# Low_jitter_CLK_bypass.net
KiCad netlist of a schematic drawn in Altium Designer
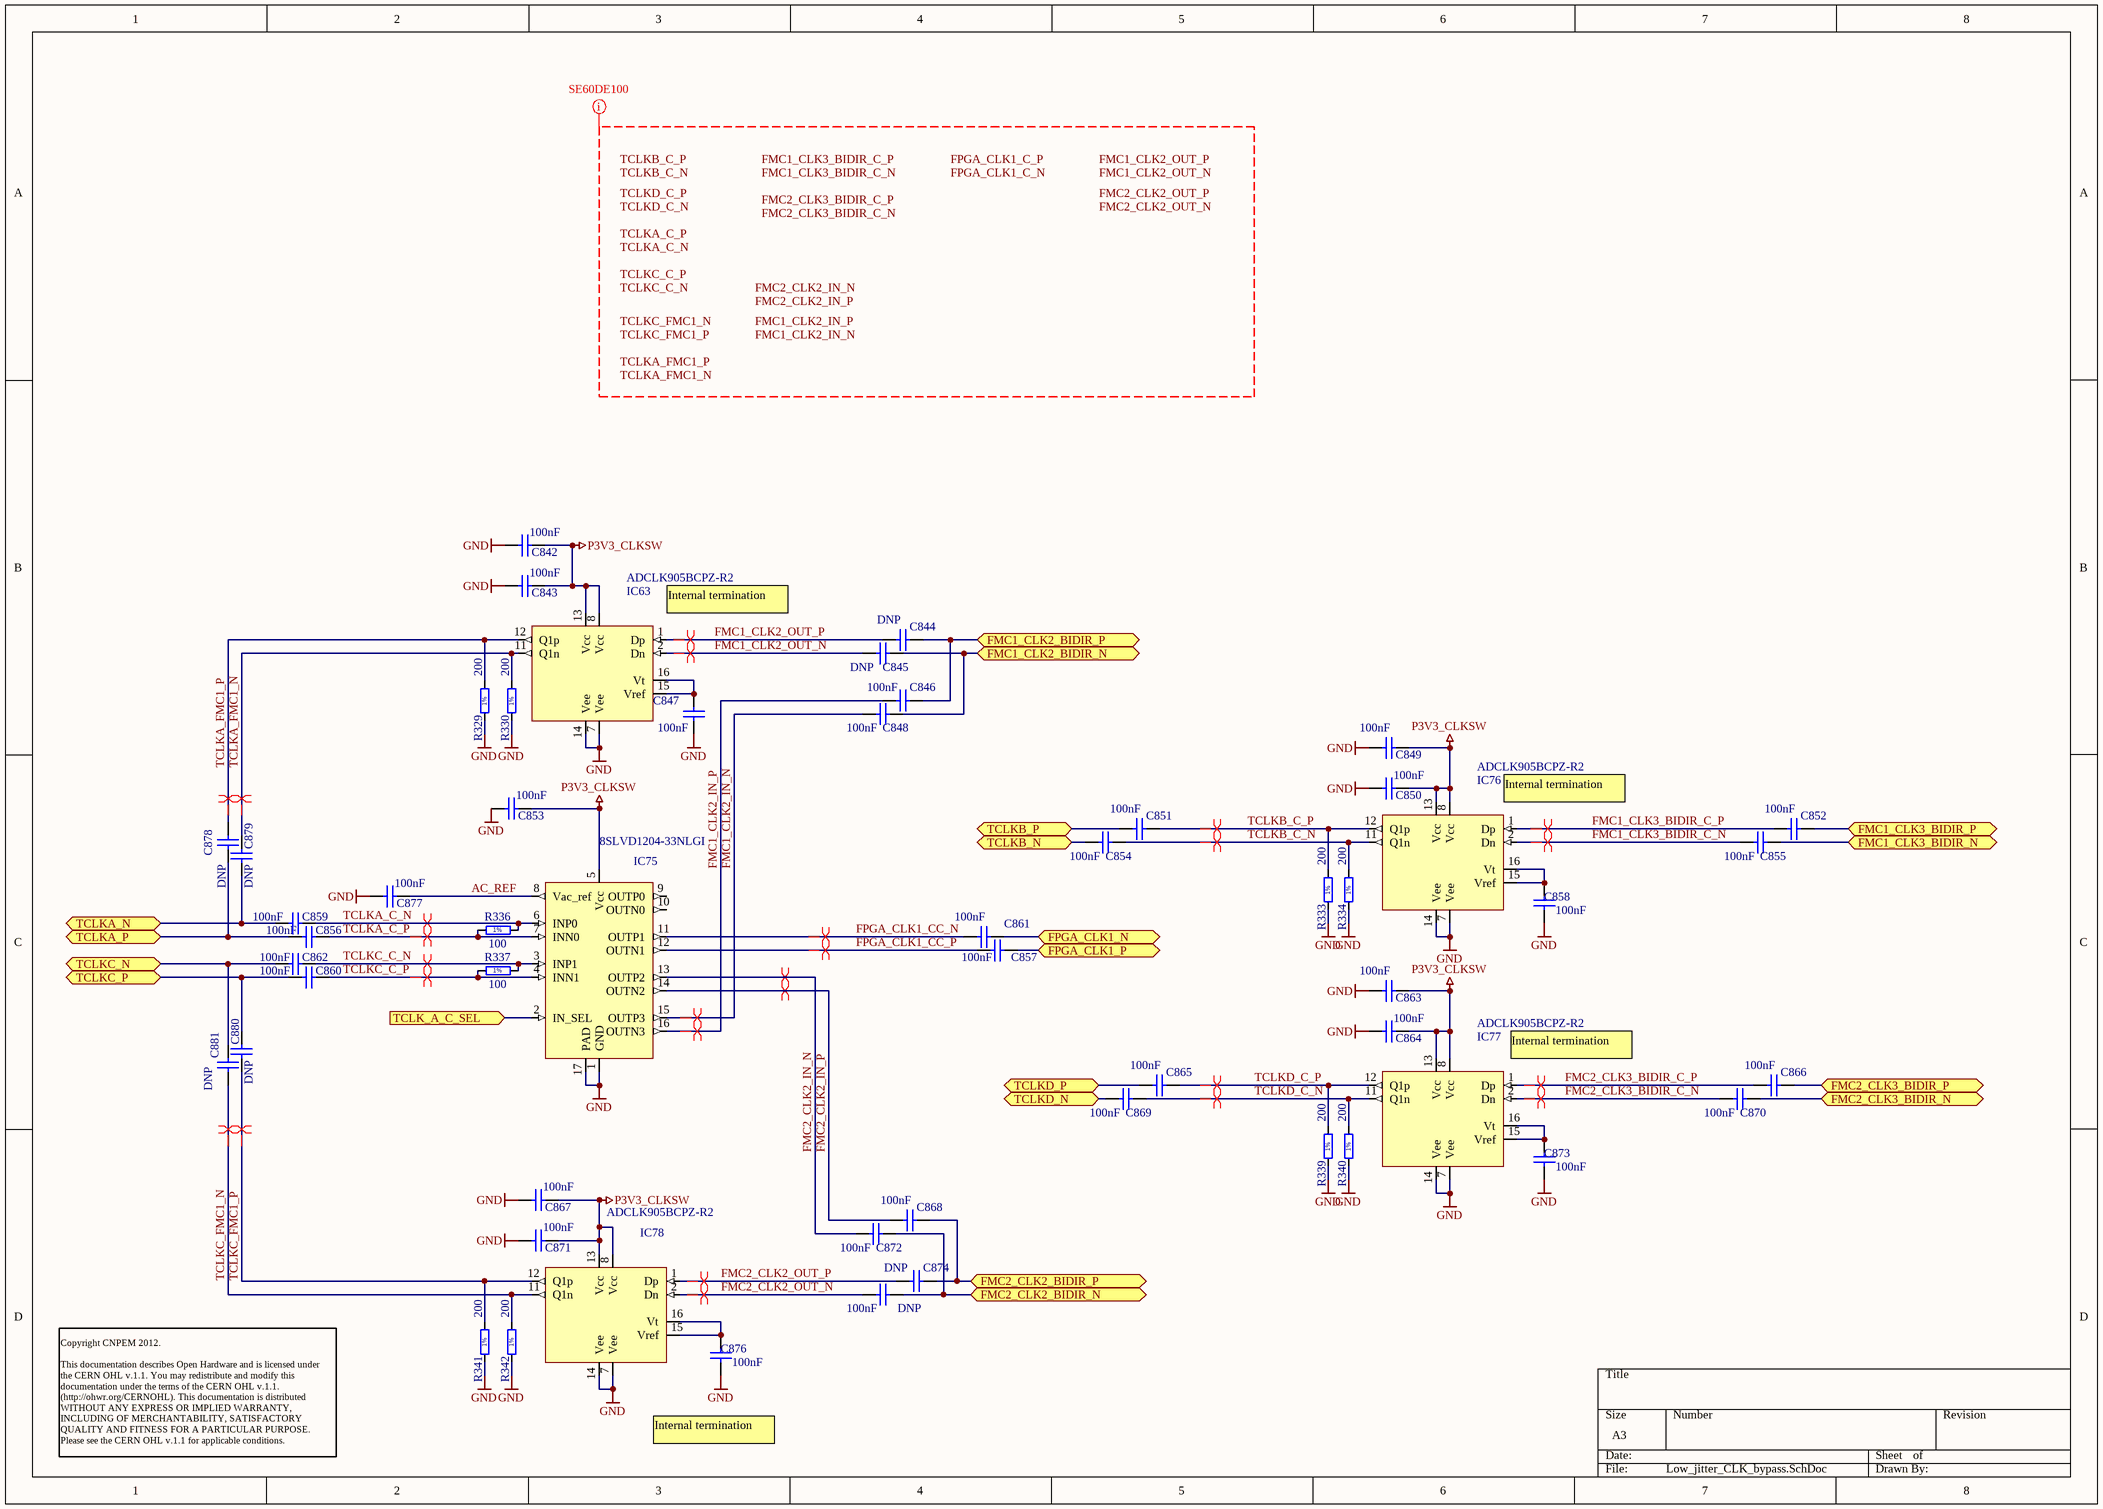
[diagram p0: Low_jitter_CLK_bypass.SchDoc]

(export (version "E")
  (design (tool "Eeschema 10.0.6"))
  (components
    (comp (ref "C842")
      (value "100nF")
      (footprint "CAPC0603X33N")
      (description "Non-polarised capacitor")
      (fields
        (field (name "PART NUMBER") "CC0201_100NF_6.3V_10%_X5R")
        (field (name "VOLTAGE") "6.3V")
        (field (name "AUTHOR") "CERN DEM JLC")
      )
      (libsource (lib "Capacitors") (part "Capacitor - non polarized"))
    )
    (comp (ref "C843")
      (value "100nF")
      (footprint "CAPC0603X33N")
      (description "Non-polarised capacitor")
      (fields
        (field (name "PART NUMBER") "CC0201_100NF_6.3V_10%_X5R")
        (field (name "VOLTAGE") "6.3V")
        (field (name "AUTHOR") "CERN DEM JLC")
      )
      (libsource (lib "Capacitors") (part "Capacitor - non polarized"))
    )
    (comp (ref "C844")
      (value "DNP")
      (footprint "CAPC0603X33N")
      (description "Non-polarised capacitor")
      (fields
        (field (name "PART NUMBER") "CC0201_100NF_6.3V_10%_X5R")
        (field (name "VOLTAGE") "6.3V")
        (field (name "AUTHOR") "CERN DEM JLC")
      )
      (libsource (lib "Capacitors") (part "Capacitor - non polarized"))
    )
    (comp (ref "C845")
      (value "DNP")
      (footprint "CAPC0603X33N")
      (description "Non-polarised capacitor")
      (fields
        (field (name "PART NUMBER") "CC0201_100NF_6.3V_10%_X5R")
        (field (name "VOLTAGE") "6.3V")
        (field (name "AUTHOR") "CERN DEM JLC")
      )
      (libsource (lib "Capacitors") (part "Capacitor - non polarized"))
    )
    (comp (ref "C846")
      (value "100nF")
      (footprint "CAPC0603X33N")
      (description "Non-polarised capacitor")
      (fields
        (field (name "PART NUMBER") "CC0201_100NF_6.3V_10%_X5R")
        (field (name "VOLTAGE") "6.3V")
        (field (name "AUTHOR") "CERN DEM JLC")
      )
      (libsource (lib "Capacitors") (part "Capacitor - non polarized"))
    )
    (comp (ref "C847")
      (value "100nF")
      (footprint "CAPC0603X33N")
      (description "Non-polarised capacitor")
      (fields
        (field (name "PART NUMBER") "CC0201_100NF_6.3V_10%_X5R")
        (field (name "VOLTAGE") "6.3V")
        (field (name "AUTHOR") "CERN DEM JLC")
      )
      (libsource (lib "Capacitors") (part "Capacitor - non polarized"))
    )
    (comp (ref "C848")
      (value "100nF")
      (footprint "CAPC0603X33N")
      (description "Non-polarised capacitor")
      (fields
        (field (name "PART NUMBER") "CC0201_100NF_6.3V_10%_X5R")
        (field (name "VOLTAGE") "6.3V")
        (field (name "AUTHOR") "CERN DEM JLC")
      )
      (libsource (lib "Capacitors") (part "Capacitor - non polarized"))
    )
    (comp (ref "C849")
      (value "100nF")
      (footprint "CAPC0603X33N")
      (description "Non-polarised capacitor")
      (fields
        (field (name "PART NUMBER") "CC0201_100NF_6.3V_10%_X5R")
        (field (name "VOLTAGE") "6.3V")
        (field (name "AUTHOR") "CERN DEM JLC")
      )
      (libsource (lib "Capacitors") (part "Capacitor - non polarized"))
    )
    (comp (ref "C850")
      (value "100nF")
      (footprint "CAPC0603X33N")
      (description "Non-polarised capacitor")
      (fields
        (field (name "PART NUMBER") "CC0201_100NF_6.3V_10%_X5R")
        (field (name "VOLTAGE") "6.3V")
        (field (name "AUTHOR") "CERN DEM JLC")
      )
      (libsource (lib "Capacitors") (part "Capacitor - non polarized"))
    )
    (comp (ref "C851")
      (value "100nF")
      (footprint "CAPC0603X33N")
      (description "Non-polarised capacitor")
      (fields
        (field (name "PART NUMBER") "CC0201_100NF_6.3V_10%_X5R")
        (field (name "VOLTAGE") "6.3V")
        (field (name "AUTHOR") "CERN DEM JLC")
      )
      (libsource (lib "Capacitors") (part "Capacitor - non polarized"))
    )
    (comp (ref "C852")
      (value "100nF")
      (footprint "CAPC0603X33N")
      (description "Non-polarised capacitor")
      (fields
        (field (name "PART NUMBER") "CC0201_100NF_6.3V_10%_X5R")
        (field (name "VOLTAGE") "6.3V")
        (field (name "AUTHOR") "CERN DEM JLC")
      )
      (libsource (lib "Capacitors") (part "Capacitor - non polarized"))
    )
    (comp (ref "C853")
      (value "100nF")
      (footprint "CAPC0603X33N")
      (description "Non-polarised capacitor")
      (fields
        (field (name "PART NUMBER") "CC0201_100NF_6.3V_10%_X5R")
        (field (name "VOLTAGE") "6.3V")
        (field (name "AUTHOR") "CERN DEM JLC")
      )
      (libsource (lib "Capacitors") (part "Capacitor - non polarized"))
    )
    (comp (ref "C854")
      (value "100nF")
      (footprint "CAPC0603X33N")
      (description "Non-polarised capacitor")
      (fields
        (field (name "PART NUMBER") "CC0201_100NF_6.3V_10%_X5R")
        (field (name "VOLTAGE") "6.3V")
        (field (name "AUTHOR") "CERN DEM JLC")
      )
      (libsource (lib "Capacitors") (part "Capacitor - non polarized"))
    )
    (comp (ref "C855")
      (value "100nF")
      (footprint "CAPC0603X33N")
      (description "Non-polarised capacitor")
      (fields
        (field (name "PART NUMBER") "CC0201_100NF_6.3V_10%_X5R")
        (field (name "VOLTAGE") "6.3V")
        (field (name "AUTHOR") "CERN DEM JLC")
      )
      (libsource (lib "Capacitors") (part "Capacitor - non polarized"))
    )
    (comp (ref "C856")
      (value "100nF")
      (footprint "CAPC0603X33N")
      (description "Non-polarised capacitor")
      (fields
        (field (name "PART NUMBER") "CC0201_100NF_6.3V_10%_X5R")
        (field (name "VOLTAGE") "6.3V")
        (field (name "AUTHOR") "CERN DEM JLC")
      )
      (libsource (lib "Capacitors") (part "Capacitor - non polarized"))
    )
    (comp (ref "C857")
      (value "100nF")
      (footprint "CAPC0603X33N")
      (description "Non-polarised capacitor")
      (fields
        (field (name "PART NUMBER") "CC0201_100NF_6.3V_10%_X5R")
        (field (name "VOLTAGE") "6.3V")
        (field (name "AUTHOR") "CERN DEM JLC")
      )
      (libsource (lib "Capacitors") (part "Capacitor - non polarized"))
    )
    (comp (ref "C858")
      (value "100nF")
      (footprint "CAPC0603X33N")
      (description "Non-polarised capacitor")
      (fields
        (field (name "PART NUMBER") "CC0201_100NF_6.3V_10%_X5R")
        (field (name "VOLTAGE") "6.3V")
        (field (name "AUTHOR") "CERN DEM JLC")
      )
      (libsource (lib "Capacitors") (part "Capacitor - non polarized"))
    )
    (comp (ref "C859")
      (value "100nF")
      (footprint "CAPC0603X33N")
      (description "Non-polarised capacitor")
      (fields
        (field (name "PART NUMBER") "CC0201_100NF_6.3V_10%_X5R")
        (field (name "VOLTAGE") "6.3V")
        (field (name "AUTHOR") "CERN DEM JLC")
      )
      (libsource (lib "Capacitors") (part "Capacitor - non polarized"))
    )
    (comp (ref "C860")
      (value "100nF")
      (footprint "CAPC0603X33N")
      (description "Non-polarised capacitor")
      (fields
        (field (name "PART NUMBER") "CC0201_100NF_6.3V_10%_X5R")
        (field (name "VOLTAGE") "6.3V")
        (field (name "AUTHOR") "CERN DEM JLC")
      )
      (libsource (lib "Capacitors") (part "Capacitor - non polarized"))
    )
    (comp (ref "C861")
      (value "100nF")
      (footprint "CAPC0603X33N")
      (description "Non-polarised capacitor")
      (fields
        (field (name "PART NUMBER") "CC0201_100NF_6.3V_10%_X5R")
        (field (name "VOLTAGE") "6.3V")
        (field (name "AUTHOR") "CERN DEM JLC")
      )
      (libsource (lib "Capacitors") (part "Capacitor - non polarized"))
    )
    (comp (ref "C862")
      (value "100nF")
      (footprint "CAPC0603X33N")
      (description "Non-polarised capacitor")
      (fields
        (field (name "PART NUMBER") "CC0201_100NF_6.3V_10%_X5R")
        (field (name "VOLTAGE") "6.3V")
        (field (name "AUTHOR") "CERN DEM JLC")
      )
      (libsource (lib "Capacitors") (part "Capacitor - non polarized"))
    )
    (comp (ref "C863")
      (value "100nF")
      (footprint "CAPC0603X33N")
      (description "Non-polarised capacitor")
      (fields
        (field (name "PART NUMBER") "CC0201_100NF_6.3V_10%_X5R")
        (field (name "VOLTAGE") "6.3V")
        (field (name "AUTHOR") "CERN DEM JLC")
      )
      (libsource (lib "Capacitors") (part "Capacitor - non polarized"))
    )
    (comp (ref "C864")
      (value "100nF")
      (footprint "CAPC0603X33N")
      (description "Non-polarised capacitor")
      (fields
        (field (name "PART NUMBER") "CC0201_100NF_6.3V_10%_X5R")
        (field (name "VOLTAGE") "6.3V")
        (field (name "AUTHOR") "CERN DEM JLC")
      )
      (libsource (lib "Capacitors") (part "Capacitor - non polarized"))
    )
    (comp (ref "C865")
      (value "100nF")
      (footprint "CAPC0603X33N")
      (description "Non-polarised capacitor")
      (fields
        (field (name "PART NUMBER") "CC0201_100NF_6.3V_10%_X5R")
        (field (name "VOLTAGE") "6.3V")
        (field (name "AUTHOR") "CERN DEM JLC")
      )
      (libsource (lib "Capacitors") (part "Capacitor - non polarized"))
    )
    (comp (ref "C866")
      (value "100nF")
      (footprint "CAPC0603X33N")
      (description "Non-polarised capacitor")
      (fields
        (field (name "PART NUMBER") "CC0201_100NF_6.3V_10%_X5R")
        (field (name "VOLTAGE") "6.3V")
        (field (name "AUTHOR") "CERN DEM JLC")
      )
      (libsource (lib "Capacitors") (part "Capacitor - non polarized"))
    )
    (comp (ref "C867")
      (value "100nF")
      (footprint "CAPC0603X33N")
      (description "Non-polarised capacitor")
      (fields
        (field (name "PART NUMBER") "CC0201_100NF_6.3V_10%_X5R")
        (field (name "VOLTAGE") "6.3V")
        (field (name "AUTHOR") "CERN DEM JLC")
      )
      (libsource (lib "Capacitors") (part "Capacitor - non polarized"))
    )
    (comp (ref "C868")
      (value "100nF")
      (footprint "CAPC0603X33N")
      (description "Non-polarised capacitor")
      (fields
        (field (name "PART NUMBER") "CC0201_100NF_6.3V_10%_X5R")
        (field (name "VOLTAGE") "6.3V")
        (field (name "AUTHOR") "CERN DEM JLC")
      )
      (libsource (lib "Capacitors") (part "Capacitor - non polarized"))
    )
    (comp (ref "C869")
      (value "100nF")
      (footprint "CAPC0603X33N")
      (description "Non-polarised capacitor")
      (fields
        (field (name "PART NUMBER") "CC0201_100NF_6.3V_10%_X5R")
        (field (name "VOLTAGE") "6.3V")
        (field (name "AUTHOR") "CERN DEM JLC")
      )
      (libsource (lib "Capacitors") (part "Capacitor - non polarized"))
    )
    (comp (ref "C870")
      (value "100nF")
      (footprint "CAPC0603X33N")
      (description "Non-polarised capacitor")
      (fields
        (field (name "PART NUMBER") "CC0201_100NF_6.3V_10%_X5R")
        (field (name "VOLTAGE") "6.3V")
        (field (name "AUTHOR") "CERN DEM JLC")
      )
      (libsource (lib "Capacitors") (part "Capacitor - non polarized"))
    )
    (comp (ref "C871")
      (value "100nF")
      (footprint "CAPC0603X33N")
      (description "Non-polarised capacitor")
      (fields
        (field (name "PART NUMBER") "CC0201_100NF_6.3V_10%_X5R")
        (field (name "VOLTAGE") "6.3V")
        (field (name "AUTHOR") "CERN DEM JLC")
      )
      (libsource (lib "Capacitors") (part "Capacitor - non polarized"))
    )
    (comp (ref "C872")
      (value "100nF")
      (footprint "CAPC0603X33N")
      (description "Non-polarised capacitor")
      (fields
        (field (name "PART NUMBER") "CC0201_100NF_6.3V_10%_X5R")
        (field (name "VOLTAGE") "6.3V")
        (field (name "AUTHOR") "CERN DEM JLC")
      )
      (libsource (lib "Capacitors") (part "Capacitor - non polarized"))
    )
    (comp (ref "C873")
      (value "100nF")
      (footprint "CAPC0603X33N")
      (description "Non-polarised capacitor")
      (fields
        (field (name "PART NUMBER") "CC0201_100NF_6.3V_10%_X5R")
        (field (name "VOLTAGE") "6.3V")
        (field (name "AUTHOR") "CERN DEM JLC")
      )
      (libsource (lib "Capacitors") (part "Capacitor - non polarized"))
    )
    (comp (ref "C874")
      (value "DNP")
      (footprint "CAPC0603X33N")
      (description "Non-polarised capacitor")
      (fields
        (field (name "PART NUMBER") "CC0201_100NF_6.3V_10%_X5R")
        (field (name "VOLTAGE") "6.3V")
        (field (name "AUTHOR") "CERN DEM JLC")
      )
      (libsource (lib "Capacitors") (part "Capacitor - non polarized"))
    )
    (comp (ref "C876")
      (value "100nF")
      (footprint "CAPC0603X33N")
      (description "Non-polarised capacitor")
      (fields
        (field (name "PART NUMBER") "CC0201_100NF_6.3V_10%_X5R")
        (field (name "VOLTAGE") "6.3V")
        (field (name "AUTHOR") "CERN DEM JLC")
      )
      (libsource (lib "Capacitors") (part "Capacitor - non polarized"))
    )
    (comp (ref "C877")
      (value "100nF")
      (footprint "CAPC0603X33N")
      (description "Non-polarised capacitor")
      (fields
        (field (name "PART NUMBER") "CC0201_100NF_6.3V_10%_X5R")
        (field (name "VOLTAGE") "6.3V")
        (field (name "AUTHOR") "CERN DEM JLC")
      )
      (libsource (lib "Capacitors") (part "Capacitor - non polarized"))
    )
    (comp (ref "C878")
      (value "DNP")
      (footprint "CAPC0603X33N")
      (description "Non-polarised capacitor")
      (fields
        (field (name "PART NUMBER") "CC0201_100NF_6.3V_10%_X5R")
        (field (name "VOLTAGE") "6.3V")
        (field (name "AUTHOR") "CERN DEM JLC")
      )
      (libsource (lib "Capacitors") (part "Capacitor - non polarized"))
    )
    (comp (ref "C879")
      (value "DNP")
      (footprint "CAPC0603X33N")
      (description "Non-polarised capacitor")
      (fields
        (field (name "PART NUMBER") "CC0201_100NF_6.3V_10%_X5R")
        (field (name "VOLTAGE") "6.3V")
        (field (name "AUTHOR") "CERN DEM JLC")
      )
      (libsource (lib "Capacitors") (part "Capacitor - non polarized"))
    )
    (comp (ref "C880")
      (value "DNP")
      (footprint "CAPC0603X33N")
      (description "Non-polarised capacitor")
      (fields
        (field (name "PART NUMBER") "CC0201_100NF_6.3V_10%_X5R")
        (field (name "VOLTAGE") "6.3V")
        (field (name "AUTHOR") "CERN DEM JLC")
      )
      (libsource (lib "Capacitors") (part "Capacitor - non polarized"))
    )
    (comp (ref "C881")
      (value "DNP")
      (footprint "CAPC0603X33N")
      (description "Non-polarised capacitor")
      (fields
        (field (name "PART NUMBER") "CC0201_100NF_6.3V_10%_X5R")
        (field (name "VOLTAGE") "6.3V")
        (field (name "AUTHOR") "CERN DEM JLC")
      )
      (libsource (lib "Capacitors") (part "Capacitor - non polarized"))
    )
    (comp (ref "DNP")
      (value "100nF")
      (footprint "CAPC0603X33N")
      (description "Non-polarised capacitor")
      (fields
        (field (name "PART NUMBER") "CC0201_100NF_6.3V_10%_X5R")
        (field (name "VOLTAGE") "6.3V")
        (field (name "AUTHOR") "CERN DEM JLC")
      )
      (libsource (lib "Capacitors") (part "Capacitor - non polarized"))
    )
    (comp (ref "IC63")
      (value "ADCLK905BCPZ-R2")
      (footprint "CP-16-3")
      (description "clock distributor")
      (libsource (lib "LIBRARY_SCH") (part "CLOCK_ADCLK905"))
    )
    (comp (ref "IC75")
      (value "8SLVD1204-33NLGI")
      (footprint "QFN50P300X300X100-16N")
      (description "2:4, LVDS Output Fanout Buffer, 3.3V")
      (libsource (lib "LIBRARY_SCH") (part "CLOCK_IDT8SLVD1204-33"))
    )
    (comp (ref "IC76")
      (value "ADCLK905BCPZ-R2")
      (footprint "CP-16-3")
      (description "clock distributor")
      (libsource (lib "LIBRARY_SCH") (part "CLOCK_ADCLK905"))
    )
    (comp (ref "IC77")
      (value "ADCLK905BCPZ-R2")
      (footprint "CP-16-3")
      (description "clock distributor")
      (libsource (lib "LIBRARY_SCH") (part "CLOCK_ADCLK905"))
    )
    (comp (ref "IC78")
      (value "ADCLK905BCPZ-R2")
      (footprint "CP-16-3")
      (description "clock distributor")
      (libsource (lib "LIBRARY_SCH") (part "CLOCK_ADCLK905"))
    )
    (comp (ref "R329")
      (value "200")
      (footprint "RESC1005X40N")
      (description "Resistor - 1%")
      (fields
        (field (name "PART NUMBER") "R0402_200R_1%_0.0625W_100PPM")
        (field (name "POWER") "0.0625W")
        (field (name "AUTHOR") "CERN DEM JLC")
      )
      (libsource (lib "Resistors") (part "Resistor - 1%"))
    )
    (comp (ref "R330")
      (value "200")
      (footprint "RESC1005X40N")
      (description "Resistor - 1%")
      (fields
        (field (name "PART NUMBER") "R0402_200R_1%_0.0625W_100PPM")
        (field (name "POWER") "0.0625W")
        (field (name "AUTHOR") "CERN DEM JLC")
      )
      (libsource (lib "Resistors") (part "Resistor - 1%"))
    )
    (comp (ref "R333")
      (value "200")
      (footprint "RESC1005X40N")
      (description "Resistor - 1%")
      (fields
        (field (name "PART NUMBER") "R0402_200R_1%_0.0625W_100PPM")
        (field (name "POWER") "0.0625W")
        (field (name "AUTHOR") "CERN DEM JLC")
      )
      (libsource (lib "Resistors") (part "Resistor - 1%"))
    )
    (comp (ref "R334")
      (value "200")
      (footprint "RESC1005X40N")
      (description "Resistor - 1%")
      (fields
        (field (name "PART NUMBER") "R0402_200R_1%_0.0625W_100PPM")
        (field (name "POWER") "0.0625W")
        (field (name "AUTHOR") "CERN DEM JLC")
      )
      (libsource (lib "Resistors") (part "Resistor - 1%"))
    )
    (comp (ref "R336")
      (value "100")
      (footprint "RESC1005X40N")
      (description "Resistor - 1%")
      (fields
        (field (name "PART NUMBER") "R0402_100R_1%_0.0625W_100PPM")
        (field (name "POWER") "0.0625W")
        (field (name "AUTHOR") "CERN DEM JLC")
      )
      (libsource (lib "Resistors") (part "Resistor - 1%"))
    )
    (comp (ref "R337")
      (value "100")
      (footprint "RESC1005X40N")
      (description "Resistor - 1%")
      (fields
        (field (name "PART NUMBER") "R0402_100R_1%_0.0625W_100PPM")
        (field (name "POWER") "0.0625W")
        (field (name "AUTHOR") "CERN DEM JLC")
      )
      (libsource (lib "Resistors") (part "Resistor - 1%"))
    )
    (comp (ref "R339")
      (value "200")
      (footprint "RESC1005X40N")
      (description "Resistor - 1%")
      (fields
        (field (name "PART NUMBER") "R0402_200R_1%_0.0625W_100PPM")
        (field (name "POWER") "0.0625W")
        (field (name "AUTHOR") "CERN DEM JLC")
      )
      (libsource (lib "Resistors") (part "Resistor - 1%"))
    )
    (comp (ref "R340")
      (value "200")
      (footprint "RESC1005X40N")
      (description "Resistor - 1%")
      (fields
        (field (name "PART NUMBER") "R0402_200R_1%_0.0625W_100PPM")
        (field (name "POWER") "0.0625W")
        (field (name "AUTHOR") "CERN DEM JLC")
      )
      (libsource (lib "Resistors") (part "Resistor - 1%"))
    )
    (comp (ref "R341")
      (value "200")
      (footprint "RESC1005X40N")
      (description "Resistor - 1%")
      (fields
        (field (name "PART NUMBER") "R0402_200R_1%_0.0625W_100PPM")
        (field (name "POWER") "0.0625W")
        (field (name "AUTHOR") "CERN DEM JLC")
      )
      (libsource (lib "Resistors") (part "Resistor - 1%"))
    )
    (comp (ref "R342")
      (value "200")
      (footprint "RESC1005X40N")
      (description "Resistor - 1%")
      (fields
        (field (name "PART NUMBER") "R0402_200R_1%_0.0625W_100PPM")
        (field (name "POWER") "0.0625W")
        (field (name "AUTHOR") "CERN DEM JLC")
      )
      (libsource (lib "Resistors") (part "Resistor - 1%"))
    )
  )
  (nets
    (net (code "1") (name "/AC_REF") (class "Default")
      (node (ref "C877") (pin "2") (pinfunction "2_2") (pintype "passive"))
      (node (ref "IC75") (pin "8") (pinfunction "Vac_ref_8") (pintype "output"))
    )
    (net (code "2") (name "/FMC1_CLK2_BIDIR_N") (class "Default")
      (node (ref "C845") (pin "2") (pinfunction "2_2") (pintype "passive"))
      (node (ref "C848") (pin "2") (pinfunction "2_2") (pintype "passive"))
    )
    (net (code "3") (name "/FMC1_CLK2_BIDIR_P") (class "Default")
      (node (ref "C844") (pin "2") (pinfunction "2_2") (pintype "passive"))
      (node (ref "C846") (pin "2") (pinfunction "2_2") (pintype "passive"))
    )
    (net (code "4") (name "/FMC1_CLK2_IN_N") (class "Default")
      (node (ref "C848") (pin "1") (pinfunction "1_1") (pintype "passive"))
      (node (ref "IC75") (pin "15") (pinfunction "OUTP3_15") (pintype "output"))
    )
    (net (code "5") (name "/FMC1_CLK2_IN_P") (class "Default")
      (node (ref "C846") (pin "1") (pinfunction "1_1") (pintype "passive"))
      (node (ref "IC75") (pin "16") (pinfunction "OUTN3_16") (pintype "output"))
    )
    (net (code "6") (name "/FMC1_CLK2_OUT_N") (class "Default")
      (node (ref "C845") (pin "1") (pinfunction "1_1") (pintype "passive"))
      (node (ref "IC63") (pin "2") (pinfunction "Dn_2") (pintype "input"))
    )
    (net (code "7") (name "/FMC1_CLK2_OUT_P") (class "Default")
      (node (ref "C844") (pin "1") (pinfunction "1_1") (pintype "passive"))
      (node (ref "IC63") (pin "1") (pinfunction "Dp_1") (pintype "input"))
    )
    (net (code "8") (name "/FMC1_CLK3_BIDIR_C_N") (class "Default")
      (node (ref "C855") (pin "1") (pinfunction "1_1") (pintype "passive"))
      (node (ref "IC76") (pin "2") (pinfunction "Dn_2") (pintype "input"))
    )
    (net (code "9") (name "/FMC1_CLK3_BIDIR_C_P") (class "Default")
      (node (ref "C852") (pin "1") (pinfunction "1_1") (pintype "passive"))
      (node (ref "IC76") (pin "1") (pinfunction "Dp_1") (pintype "input"))
    )
    (net (code "10") (name "/FMC1_CLK3_BIDIR_N") (class "Default")
      (node (ref "C855") (pin "2") (pinfunction "2_2") (pintype "passive"))
    )
    (net (code "11") (name "/FMC1_CLK3_BIDIR_P") (class "Default")
      (node (ref "C852") (pin "2") (pinfunction "2_2") (pintype "passive"))
    )
    (net (code "12") (name "/FMC2_CLK2_BIDIR_N") (class "Default")
      (node (ref "C872") (pin "2") (pinfunction "2_2") (pintype "passive"))
      (node (ref "DNP") (pin "2") (pinfunction "2_2") (pintype "passive"))
    )
    (net (code "13") (name "/FMC2_CLK2_BIDIR_P") (class "Default")
      (node (ref "C868") (pin "2") (pinfunction "2_2") (pintype "passive"))
      (node (ref "C874") (pin "2") (pinfunction "2_2") (pintype "passive"))
    )
    (net (code "14") (name "/FMC2_CLK2_IN_N") (class "Default")
      (node (ref "C872") (pin "1") (pinfunction "1_1") (pintype "passive"))
      (node (ref "IC75") (pin "13") (pinfunction "OUTP2_13") (pintype "output"))
    )
    (net (code "15") (name "/FMC2_CLK2_IN_P") (class "Default")
      (node (ref "C868") (pin "1") (pinfunction "1_1") (pintype "passive"))
      (node (ref "IC75") (pin "14") (pinfunction "OUTN2_14") (pintype "output"))
    )
    (net (code "16") (name "/FMC2_CLK2_OUT_N") (class "Default")
      (node (ref "DNP") (pin "1") (pinfunction "1_1") (pintype "passive"))
      (node (ref "IC78") (pin "2") (pinfunction "Dn_2") (pintype "input"))
    )
    (net (code "17") (name "/FMC2_CLK2_OUT_P") (class "Default")
      (node (ref "C874") (pin "1") (pinfunction "1_1") (pintype "passive"))
      (node (ref "IC78") (pin "1") (pinfunction "Dp_1") (pintype "input"))
    )
    (net (code "18") (name "/FMC2_CLK3_BIDIR_C_N") (class "Default")
      (node (ref "C870") (pin "1") (pinfunction "1_1") (pintype "passive"))
      (node (ref "IC77") (pin "2") (pinfunction "Dn_2") (pintype "input"))
    )
    (net (code "19") (name "/FMC2_CLK3_BIDIR_C_P") (class "Default")
      (node (ref "C866") (pin "1") (pinfunction "1_1") (pintype "passive"))
      (node (ref "IC77") (pin "1") (pinfunction "Dp_1") (pintype "input"))
    )
    (net (code "20") (name "/FMC2_CLK3_BIDIR_N") (class "Default")
      (node (ref "C870") (pin "2") (pinfunction "2_2") (pintype "passive"))
    )
    (net (code "21") (name "/FMC2_CLK3_BIDIR_P") (class "Default")
      (node (ref "C866") (pin "2") (pinfunction "2_2") (pintype "passive"))
    )
    (net (code "22") (name "/FPGA_CLK1_CC_N") (class "Default")
      (node (ref "C861") (pin "1") (pinfunction "1_1") (pintype "passive"))
      (node (ref "IC75") (pin "11") (pinfunction "OUTP1_11") (pintype "output"))
    )
    (net (code "23") (name "/FPGA_CLK1_CC_P") (class "Default")
      (node (ref "C857") (pin "1") (pinfunction "1_1") (pintype "passive"))
      (node (ref "IC75") (pin "12") (pinfunction "OUTN1_12") (pintype "output"))
    )
    (net (code "26") (name "/FPGA_CLK1_N") (class "Default")
      (node (ref "C861") (pin "2") (pinfunction "2_2") (pintype "passive"))
    )
    (net (code "27") (name "/FPGA_CLK1_P") (class "Default")
      (node (ref "C857") (pin "2") (pinfunction "2_2") (pintype "passive"))
    )
    (net (code "28") (name "/TCLKA_C_N") (class "Default")
      (node (ref "C859") (pin "2") (pinfunction "2_2") (pintype "passive"))
      (node (ref "IC75") (pin "6") (pinfunction "INP0_6") (pintype "input"))
      (node (ref "R336") (pin "2") (pinfunction "2_2") (pintype "passive"))
    )
    (net (code "29") (name "/TCLKA_C_P") (class "Default")
      (node (ref "C856") (pin "2") (pinfunction "2_2") (pintype "passive"))
      (node (ref "IC75") (pin "7") (pinfunction "INN0_7") (pintype "input"))
      (node (ref "R336") (pin "1") (pinfunction "1_1") (pintype "passive"))
    )
    (net (code "30") (name "/TCLKA_FMC1_N") (class "Default")
      (node (ref "C879") (pin "2") (pinfunction "2_2") (pintype "passive"))
      (node (ref "IC63") (pin "11") (pinfunction "Q1n_11") (pintype "output"))
      (node (ref "R330") (pin "2") (pinfunction "2_2") (pintype "passive"))
    )
    (net (code "31") (name "/TCLKA_FMC1_P") (class "Default")
      (node (ref "C878") (pin "2") (pinfunction "2_2") (pintype "passive"))
      (node (ref "IC63") (pin "12") (pinfunction "Q1p_12") (pintype "output"))
      (node (ref "R329") (pin "2") (pinfunction "2_2") (pintype "passive"))
    )
    (net (code "32") (name "/TCLKA_N") (class "Default")
      (node (ref "C859") (pin "1") (pinfunction "1_1") (pintype "passive"))
      (node (ref "C879") (pin "1") (pinfunction "1_1") (pintype "passive"))
    )
    (net (code "33") (name "/TCLKA_P") (class "Default")
      (node (ref "C856") (pin "1") (pinfunction "1_1") (pintype "passive"))
      (node (ref "C878") (pin "1") (pinfunction "1_1") (pintype "passive"))
    )
    (net (code "34") (name "/TCLKB_C_N") (class "Default")
      (node (ref "C854") (pin "2") (pinfunction "2_2") (pintype "passive"))
      (node (ref "IC76") (pin "11") (pinfunction "Q1n_11") (pintype "output"))
      (node (ref "R334") (pin "2") (pinfunction "2_2") (pintype "passive"))
    )
    (net (code "35") (name "/TCLKB_C_P") (class "Default")
      (node (ref "C851") (pin "2") (pinfunction "2_2") (pintype "passive"))
      (node (ref "IC76") (pin "12") (pinfunction "Q1p_12") (pintype "output"))
      (node (ref "R333") (pin "2") (pinfunction "2_2") (pintype "passive"))
    )
    (net (code "36") (name "/TCLKB_N") (class "Default")
      (node (ref "C854") (pin "1") (pinfunction "1_1") (pintype "passive"))
    )
    (net (code "37") (name "/TCLKB_P") (class "Default")
      (node (ref "C851") (pin "1") (pinfunction "1_1") (pintype "passive"))
    )
    (net (code "38") (name "/TCLKC_C_N") (class "Default")
      (node (ref "C862") (pin "2") (pinfunction "2_2") (pintype "passive"))
      (node (ref "IC75") (pin "3") (pinfunction "INP1_3") (pintype "input"))
      (node (ref "R337") (pin "2") (pinfunction "2_2") (pintype "passive"))
    )
    (net (code "39") (name "/TCLKC_C_P") (class "Default")
      (node (ref "C860") (pin "2") (pinfunction "2_2") (pintype "passive"))
      (node (ref "IC75") (pin "4") (pinfunction "INN1_4") (pintype "input"))
      (node (ref "R337") (pin "1") (pinfunction "1_1") (pintype "passive"))
    )
    (net (code "40") (name "/TCLKC_FMC1_N") (class "Default")
      (node (ref "C881") (pin "1") (pinfunction "1_1") (pintype "passive"))
      (node (ref "IC78") (pin "11") (pinfunction "Q1n_11") (pintype "output"))
      (node (ref "R342") (pin "2") (pinfunction "2_2") (pintype "passive"))
    )
    (net (code "41") (name "/TCLKC_FMC1_P") (class "Default")
      (node (ref "C880") (pin "1") (pinfunction "1_1") (pintype "passive"))
      (node (ref "IC78") (pin "12") (pinfunction "Q1p_12") (pintype "output"))
      (node (ref "R341") (pin "2") (pinfunction "2_2") (pintype "passive"))
    )
    (net (code "42") (name "/TCLKC_N") (class "Default")
      (node (ref "C862") (pin "1") (pinfunction "1_1") (pintype "passive"))
      (node (ref "C881") (pin "2") (pinfunction "2_2") (pintype "passive"))
    )
    (net (code "43") (name "/TCLKC_P") (class "Default")
      (node (ref "C860") (pin "1") (pinfunction "1_1") (pintype "passive"))
      (node (ref "C880") (pin "2") (pinfunction "2_2") (pintype "passive"))
    )
    (net (code "44") (name "/TCLKD_C_N") (class "Default")
      (node (ref "C869") (pin "2") (pinfunction "2_2") (pintype "passive"))
      (node (ref "IC77") (pin "11") (pinfunction "Q1n_11") (pintype "output"))
      (node (ref "R340") (pin "2") (pinfunction "2_2") (pintype "passive"))
    )
    (net (code "45") (name "/TCLKD_C_P") (class "Default")
      (node (ref "C865") (pin "2") (pinfunction "2_2") (pintype "passive"))
      (node (ref "IC77") (pin "12") (pinfunction "Q1p_12") (pintype "output"))
      (node (ref "R339") (pin "2") (pinfunction "2_2") (pintype "passive"))
    )
    (net (code "46") (name "/TCLKD_N") (class "Default")
      (node (ref "C869") (pin "1") (pinfunction "1_1") (pintype "passive"))
    )
    (net (code "47") (name "/TCLKD_P") (class "Default")
      (node (ref "C865") (pin "1") (pinfunction "1_1") (pintype "passive"))
    )
    (net (code "48") (name "/TCLK_A_C_SEL") (class "Default")
      (node (ref "IC75") (pin "2") (pinfunction "IN_SEL_2") (pintype "input"))
    )
    (net (code "49") (name "GND") (class "Default")
      (node (ref "C842") (pin "1") (pinfunction "1_1") (pintype "passive"))
      (node (ref "C843") (pin "1") (pinfunction "1_1") (pintype "passive"))
      (node (ref "C847") (pin "1") (pinfunction "1_1") (pintype "passive"))
      (node (ref "C849") (pin "1") (pinfunction "1_1") (pintype "passive"))
      (node (ref "C850") (pin "1") (pinfunction "1_1") (pintype "passive"))
      (node (ref "C853") (pin "1") (pinfunction "1_1") (pintype "passive"))
      (node (ref "C858") (pin "1") (pinfunction "1_1") (pintype "passive"))
      (node (ref "C863") (pin "1") (pinfunction "1_1") (pintype "passive"))
      (node (ref "C864") (pin "1") (pinfunction "1_1") (pintype "passive"))
      (node (ref "C867") (pin "1") (pinfunction "1_1") (pintype "passive"))
      (node (ref "C871") (pin "1") (pinfunction "1_1") (pintype "passive"))
      (node (ref "C873") (pin "1") (pinfunction "1_1") (pintype "passive"))
      (node (ref "C876") (pin "1") (pinfunction "1_1") (pintype "passive"))
      (node (ref "C877") (pin "1") (pinfunction "1_1") (pintype "passive"))
      (node (ref "IC63") (pin "14") (pinfunction "Vee_14") (pintype "power_in"))
      (node (ref "IC63") (pin "7") (pinfunction "Vee_7") (pintype "power_in"))
      (node (ref "IC75") (pin "1") (pinfunction "GND_1") (pintype "power_in"))
      (node (ref "IC75") (pin "17") (pinfunction "PAD_17") (pintype "power_in"))
      (node (ref "IC76") (pin "14") (pinfunction "Vee_14") (pintype "power_in"))
      (node (ref "IC76") (pin "7") (pinfunction "Vee_7") (pintype "power_in"))
      (node (ref "IC77") (pin "14") (pinfunction "Vee_14") (pintype "power_in"))
      (node (ref "IC77") (pin "7") (pinfunction "Vee_7") (pintype "power_in"))
      (node (ref "IC78") (pin "14") (pinfunction "Vee_14") (pintype "power_in"))
      (node (ref "IC78") (pin "7") (pinfunction "Vee_7") (pintype "power_in"))
      (node (ref "R329") (pin "1") (pinfunction "1_1") (pintype "passive"))
      (node (ref "R330") (pin "1") (pinfunction "1_1") (pintype "passive"))
      (node (ref "R333") (pin "1") (pinfunction "1_1") (pintype "passive"))
      (node (ref "R334") (pin "1") (pinfunction "1_1") (pintype "passive"))
      (node (ref "R339") (pin "1") (pinfunction "1_1") (pintype "passive"))
      (node (ref "R340") (pin "1") (pinfunction "1_1") (pintype "passive"))
      (node (ref "R341") (pin "1") (pinfunction "1_1") (pintype "passive"))
      (node (ref "R342") (pin "1") (pinfunction "1_1") (pintype "passive"))
    )
    (net (code "50") (name "Net-(IC63-Vref)") (class "Default")
      (node (ref "C847") (pin "2") (pinfunction "2_2") (pintype "passive"))
      (node (ref "IC63") (pin "15") (pinfunction "Vref_15") (pintype "power_in"))
      (node (ref "IC63") (pin "16") (pinfunction "Vt_16") (pintype "passive"))
    )
    (net (code "51") (name "Net-(IC76-Vref)") (class "Default")
      (node (ref "C858") (pin "2") (pinfunction "2_2") (pintype "passive"))
      (node (ref "IC76") (pin "15") (pinfunction "Vref_15") (pintype "power_in"))
      (node (ref "IC76") (pin "16") (pinfunction "Vt_16") (pintype "passive"))
    )
    (net (code "52") (name "Net-(IC77-Vref)") (class "Default")
      (node (ref "C873") (pin "2") (pinfunction "2_2") (pintype "passive"))
      (node (ref "IC77") (pin "15") (pinfunction "Vref_15") (pintype "power_in"))
      (node (ref "IC77") (pin "16") (pinfunction "Vt_16") (pintype "passive"))
    )
    (net (code "53") (name "Net-(IC78-Vref)") (class "Default")
      (node (ref "C876") (pin "2") (pinfunction "2_2") (pintype "passive"))
      (node (ref "IC78") (pin "15") (pinfunction "Vref_15") (pintype "power_in"))
      (node (ref "IC78") (pin "16") (pinfunction "Vt_16") (pintype "passive"))
    )
    (net (code "54") (name "P3V3_CLKSW") (class "Default")
      (node (ref "C842") (pin "2") (pinfunction "2_2") (pintype "passive"))
      (node (ref "C843") (pin "2") (pinfunction "2_2") (pintype "passive"))
      (node (ref "C849") (pin "2") (pinfunction "2_2") (pintype "passive"))
      (node (ref "C850") (pin "2") (pinfunction "2_2") (pintype "passive"))
      (node (ref "C853") (pin "2") (pinfunction "2_2") (pintype "passive"))
      (node (ref "C863") (pin "2") (pinfunction "2_2") (pintype "passive"))
      (node (ref "C864") (pin "2") (pinfunction "2_2") (pintype "passive"))
      (node (ref "C867") (pin "2") (pinfunction "2_2") (pintype "passive"))
      (node (ref "C871") (pin "2") (pinfunction "2_2") (pintype "passive"))
      (node (ref "IC63") (pin "13") (pinfunction "Vcc_13") (pintype "power_in"))
      (node (ref "IC63") (pin "8") (pinfunction "Vcc_8") (pintype "power_in"))
      (node (ref "IC75") (pin "5") (pinfunction "Vcc_5") (pintype "power_in"))
      (node (ref "IC76") (pin "13") (pinfunction "Vcc_13") (pintype "power_in"))
      (node (ref "IC76") (pin "8") (pinfunction "Vcc_8") (pintype "power_in"))
      (node (ref "IC77") (pin "13") (pinfunction "Vcc_13") (pintype "power_in"))
      (node (ref "IC77") (pin "8") (pinfunction "Vcc_8") (pintype "power_in"))
      (node (ref "IC78") (pin "13") (pinfunction "Vcc_13") (pintype "power_in"))
      (node (ref "IC78") (pin "8") (pinfunction "Vcc_8") (pintype "power_in"))
    )
    (net (code "55") (name "unconnected-(IC75-OUTN0-Pad10)") (class "Default")
      (node (ref "IC75") (pin "10") (pinfunction "OUTN0_10") (pintype "output"))
    )
    (net (code "56") (name "unconnected-(IC75-OUTP0-Pad9)") (class "Default")
      (node (ref "IC75") (pin "9") (pinfunction "OUTP0_9") (pintype "output"))
    )
  )
)
